# beefocus.net
KiCad netlist of a schematic drawn in EAGLE
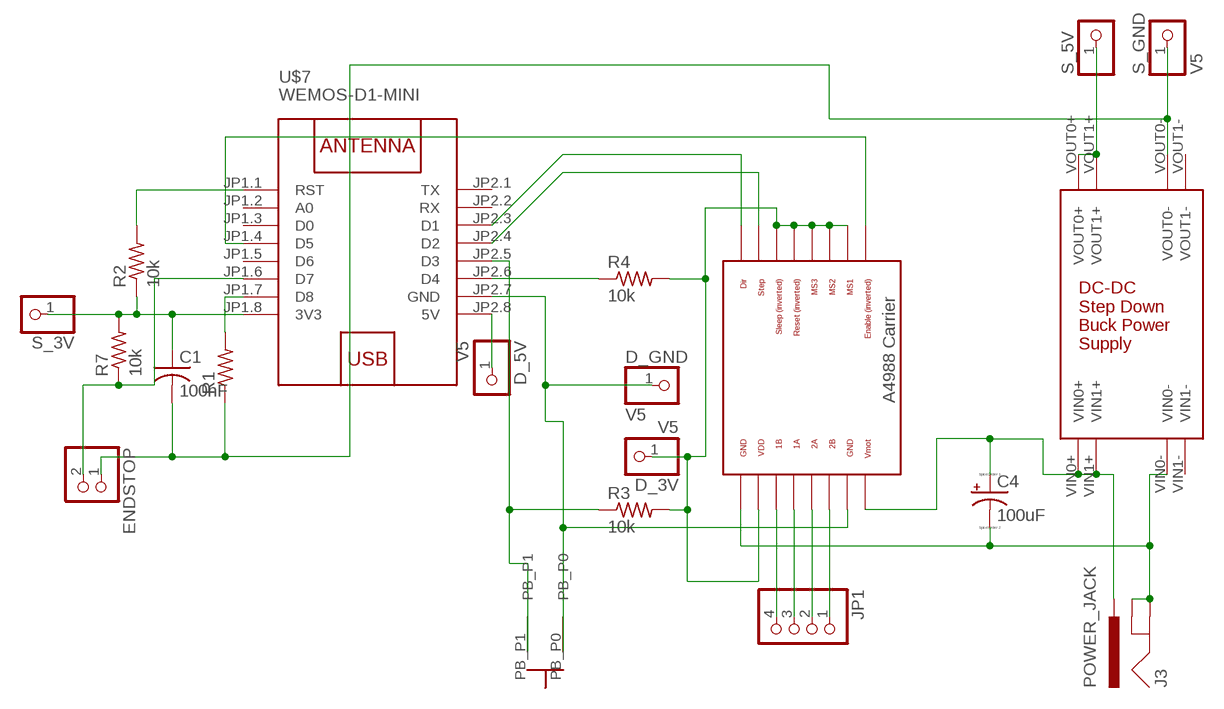
[diagram p0: schematic, sheet 1]

(export (version "E")
  (design (tool "Eeschema 10.0.6"))
  (components
    (comp (ref "C1")
      (value "100nF")
      (footprint "eagle-import:C050-024X044")
      (libsource (lib "eagle-import") (part "C-US050-024X044"))
    )
    (comp (ref "C4")
      (value "100uF")
      (footprint "eagle-import:E3,5-8")
      (libsource (lib "eagle-import") (part "CPOL-USE3.5-8"))
    )
    (comp (ref "D_3V")
      (value "V5")
      (footprint "eagle-import:1X01")
      (libsource (lib "eagle-import") (part "PINHD-1X1"))
    )
    (comp (ref "D_5V")
      (value "V5")
      (footprint "eagle-import:1X01")
      (libsource (lib "eagle-import") (part "PINHD-1X1"))
    )
    (comp (ref "D_GND")
      (value "V5")
      (footprint "eagle-import:1X01")
      (libsource (lib "eagle-import") (part "PINHD-1X1"))
    )
    (comp (ref "ENDSTOP")
      (value "PINHD-1X2/90")
      (footprint "eagle-import:1X02_90")
      (libsource (lib "eagle-import") (part "PINHD-1X2/90"))
    )
    (comp (ref "J3")
      (value "POWER_JACK")
      (footprint "eagle-import:POWER_JACK_PTH")
      (libsource (lib "eagle-import") (part "POWER_JACK"))
    )
    (comp (ref "JP1")
      (value "PINHD-1X4/90")
      (footprint "eagle-import:1X04_90")
      (libsource (lib "eagle-import") (part "PINHD-1X4/90"))
    )
    (comp (ref "R1")
      (value "R-US_0204/7")
      (footprint "eagle-import:0204_7")
      (libsource (lib "eagle-import") (part "R-US_0204/7"))
    )
    (comp (ref "R2")
      (value "10k")
      (footprint "eagle-import:0204_7")
      (libsource (lib "eagle-import") (part "R-US_0204/7"))
    )
    (comp (ref "R3")
      (value "10k")
      (footprint "eagle-import:0309V")
      (libsource (lib "eagle-import") (part "R-US_0309/V"))
    )
    (comp (ref "R4")
      (value "10k")
      (footprint "eagle-import:0204_7")
      (libsource (lib "eagle-import") (part "R-US_0204/7"))
    )
    (comp (ref "R7")
      (value "10k")
      (footprint "eagle-import:0309V")
      (libsource (lib "eagle-import") (part "R-US_0309/V"))
    )
    (comp (ref "S_3V")
      (value "PINHD-1X1")
      (footprint "eagle-import:1X01")
      (libsource (lib "eagle-import") (part "PINHD-1X1"))
    )
    (comp (ref "S_5V")
      (value "PINHD-1X1")
      (footprint "eagle-import:1X01")
      (libsource (lib "eagle-import") (part "PINHD-1X1"))
    )
    (comp (ref "S_GND")
      (value "V5")
      (footprint "eagle-import:1X01")
      (libsource (lib "eagle-import") (part "PINHD-1X1"))
    )
    (comp (ref "U$1")
      (value "POLOLU_A4983CARRIER")
      (footprint "eagle-import:A4988BREAKOUT")
      (libsource (lib "eagle-import") (part "POLOLU_A4983CARRIER"))
    )
    (comp (ref "U$6")
      (value "DCPOWERCONV")
      (footprint "eagle-import:DCPOWERCONV")
      (libsource (lib "eagle-import") (part "DCPOWERCONV"))
    )
    (comp (ref "U$7")
      (value "WEMOS-D1-MINI")
      (footprint "eagle-import:WEMOS-D1-MINI")
      (libsource (lib "eagle-import") (part "WEMOS-D1-MINI"))
    )
    (comp (ref "U$8")
      (value "BUTTON6X6X10MMSIDE")
      (footprint "eagle-import:BUTTON6X6X10MMSIDE")
      (libsource (lib "eagle-import") (part "BUTTON6X6X10MMSIDE"))
    )
  )
  (nets
    (net (code "1") (name "Net-(C1-Pad2)") (class "Default")
      (node (ref "C1") (pin "2") (pinfunction "2_2") (pintype "passive"))
      (node (ref "ENDSTOP") (pin "1") (pinfunction "1_1") (pintype "passive"))
      (node (ref "R1") (pin "1") (pinfunction "1_1") (pintype "passive"))
      (node (ref "S_GND") (pin "1") (pinfunction "1_1") (pintype "passive"))
      (node (ref "U$6") (pin "VOUT0-") (pinfunction "VOUT0-_VOUT0-") (pintype "bidirectional"))
    )
    (net (code "2") (name "Net-(C4-Pad+)") (class "Default")
      (node (ref "C4") (pin "+") (pinfunction "+_+") (pintype "passive"))
      (node (ref "J3") (pin "PWR") (pinfunction "PWR_PWR") (pintype "bidirectional"))
      (node (ref "U$1") (pin "VMOT") (pinfunction "VMOT_VMOT") (pintype "power_in"))
      (node (ref "U$6") (pin "VIN0+") (pinfunction "VIN0+_VIN0+") (pintype "bidirectional"))
      (node (ref "U$6") (pin "VIN1+") (pinfunction "VIN1+_VIN1+") (pintype "bidirectional"))
    )
    (net (code "3") (name "Net-(C4-Pad-)") (class "Default")
      (node (ref "C4") (pin "-") (pinfunction "-_-") (pintype "passive"))
      (node (ref "J3") (pin "GND") (pinfunction "GND_GND") (pintype "bidirectional"))
      (node (ref "J3") (pin "GNDBREAK") (pinfunction "GNDBREAK_GNDBREAK") (pintype "bidirectional"))
      (node (ref "U$1") (pin "GND@0") (pinfunction "GND_GND@0") (pintype "power_in"))
      (node (ref "U$6") (pin "VIN0-") (pinfunction "VIN0-_VIN0-") (pintype "bidirectional"))
    )
    (net (code "4") (name "Net-(JP1-Pad1)") (class "Default")
      (node (ref "JP1") (pin "1") (pinfunction "1_1") (pintype "passive"))
      (node (ref "U$1") (pin "2B") (pinfunction "2B_2B") (pintype "output"))
    )
    (net (code "5") (name "Net-(JP1-Pad2)") (class "Default")
      (node (ref "JP1") (pin "2") (pinfunction "2_2") (pintype "passive"))
      (node (ref "U$1") (pin "2A") (pinfunction "2A_2A") (pintype "output"))
    )
    (net (code "6") (name "Net-(JP1-Pad3)") (class "Default")
      (node (ref "JP1") (pin "3") (pinfunction "3_3") (pintype "passive"))
      (node (ref "U$1") (pin "1A") (pinfunction "1A_1A") (pintype "output"))
    )
    (net (code "7") (name "Net-(JP1-Pad4)") (class "Default")
      (node (ref "JP1") (pin "4") (pinfunction "4_4") (pintype "passive"))
      (node (ref "U$1") (pin "1B") (pinfunction "1B_1B") (pintype "output"))
    )
    (net (code "8") (name "Net-(S_5V-Pad1)") (class "Default")
      (node (ref "S_5V") (pin "1") (pinfunction "1_1") (pintype "passive"))
      (node (ref "U$6") (pin "VOUT0+") (pinfunction "VOUT0+_VOUT0+") (pintype "bidirectional"))
      (node (ref "U$6") (pin "VOUT1+") (pinfunction "VOUT1+_VOUT1+") (pintype "bidirectional"))
    )
    (net (code "9") (name "Net-(U$1-SLEEP)") (class "Default")
      (node (ref "D_3V") (pin "1") (pinfunction "1_1") (pintype "passive"))
      (node (ref "R3") (pin "2") (pinfunction "2_2") (pintype "passive"))
      (node (ref "R4") (pin "2") (pinfunction "2_2") (pintype "passive"))
      (node (ref "U$1") (pin "MS1") (pinfunction "MS1_MS1") (pintype "input"))
      (node (ref "U$1") (pin "MS2") (pinfunction "MS2_MS2") (pintype "input"))
      (node (ref "U$1") (pin "MS3") (pinfunction "MS3_MS3") (pintype "input"))
      (node (ref "U$1") (pin "RST") (pinfunction "RST_RST") (pintype "input"))
      (node (ref "U$1") (pin "SLP") (pinfunction "SLEEP_SLP") (pintype "input"))
      (node (ref "U$1") (pin "VDD") (pinfunction "VDD_VDD") (pintype "power_in"))
    )
    (net (code "10") (name "Net-(U$7-3V3)") (class "Default")
      (node (ref "C1") (pin "1") (pinfunction "1_1") (pintype "passive"))
      (node (ref "R2") (pin "1") (pinfunction "1_1") (pintype "passive"))
      (node (ref "R7") (pin "2") (pinfunction "2_2") (pintype "passive"))
      (node (ref "S_3V") (pin "1") (pinfunction "1_1") (pintype "passive"))
      (node (ref "U$7") (pin "JP1.8") (pinfunction "3V3_JP1.8") (pintype "power_in"))
    )
    (net (code "11") (name "Net-(U$7-5V)") (class "Default")
      (node (ref "D_5V") (pin "1") (pinfunction "1_1") (pintype "passive"))
      (node (ref "U$7") (pin "JP2.8") (pinfunction "5V_JP2.8") (pintype "power_in"))
    )
    (net (code "12") (name "Net-(U$7-D1)") (class "Default")
      (node (ref "U$1") (pin "DIR") (pinfunction "DIR_DIR") (pintype "input"))
      (node (ref "U$7") (pin "JP2.3") (pinfunction "D1_JP2.3") (pintype "bidirectional"))
    )
    (net (code "13") (name "Net-(U$7-D2)") (class "Default")
      (node (ref "U$1") (pin "STEP") (pinfunction "STEP_STEP") (pintype "input"))
      (node (ref "U$7") (pin "JP2.4") (pinfunction "D2_JP2.4") (pintype "bidirectional"))
    )
    (net (code "14") (name "Net-(U$7-D3)") (class "Default")
      (node (ref "R3") (pin "1") (pinfunction "1_1") (pintype "passive"))
      (node (ref "U$7") (pin "JP2.5") (pinfunction "D3_JP2.5") (pintype "bidirectional"))
      (node (ref "U$8") (pin "PB_P1") (pinfunction "PB_P1_PB_P1") (pintype "bidirectional"))
    )
    (net (code "15") (name "Net-(U$7-D4)") (class "Default")
      (node (ref "R4") (pin "1") (pinfunction "1_1") (pintype "passive"))
      (node (ref "U$7") (pin "JP2.6") (pinfunction "D4_JP2.6") (pintype "bidirectional"))
    )
    (net (code "16") (name "Net-(U$7-D5)") (class "Default")
      (node (ref "U$1") (pin "EN") (pinfunction "EN_EN") (pintype "input"))
      (node (ref "U$7") (pin "JP1.4") (pinfunction "D5_JP1.4") (pintype "bidirectional"))
    )
    (net (code "17") (name "Net-(U$7-D7)") (class "Default")
      (node (ref "ENDSTOP") (pin "2") (pinfunction "2_2") (pintype "passive"))
      (node (ref "R7") (pin "1") (pinfunction "1_1") (pintype "passive"))
      (node (ref "U$7") (pin "JP1.6") (pinfunction "D7_JP1.6") (pintype "bidirectional"))
    )
    (net (code "18") (name "Net-(U$7-D8)") (class "Default")
      (node (ref "R1") (pin "2") (pinfunction "2_2") (pintype "passive"))
      (node (ref "U$7") (pin "JP1.7") (pinfunction "D8_JP1.7") (pintype "bidirectional"))
    )
    (net (code "19") (name "Net-(U$7-GND)") (class "Default")
      (node (ref "D_GND") (pin "1") (pinfunction "1_1") (pintype "passive"))
      (node (ref "U$1") (pin "GND") (pinfunction "GND_GND") (pintype "power_in"))
      (node (ref "U$7") (pin "JP2.7") (pinfunction "GND_JP2.7") (pintype "power_in"))
      (node (ref "U$8") (pin "PB_P0") (pinfunction "PB_P0_PB_P0") (pintype "bidirectional"))
    )
    (net (code "20") (name "Net-(U$7-RST)") (class "Default")
      (node (ref "R2") (pin "2") (pinfunction "2_2") (pintype "passive"))
      (node (ref "U$7") (pin "JP1.1") (pinfunction "RST_JP1.1") (pintype "bidirectional"))
    )
    (net (code "21") (name "unconnected-(U$6-PadVIN1-)") (class "Default")
      (node (ref "U$6") (pin "VIN1-") (pinfunction "VIN1-_VIN1-") (pintype "bidirectional"))
    )
    (net (code "22") (name "unconnected-(U$6-PadVOUT1-)") (class "Default")
      (node (ref "U$6") (pin "VOUT1-") (pinfunction "VOUT1-_VOUT1-") (pintype "bidirectional"))
    )
    (net (code "23") (name "unconnected-(U$7-A0-PadJP1.2)") (class "Default")
      (node (ref "U$7") (pin "JP1.2") (pinfunction "A0_JP1.2") (pintype "bidirectional"))
    )
    (net (code "24") (name "unconnected-(U$7-D0-PadJP1.3)") (class "Default")
      (node (ref "U$7") (pin "JP1.3") (pinfunction "D0_JP1.3") (pintype "bidirectional"))
    )
    (net (code "25") (name "unconnected-(U$7-D6-PadJP1.5)") (class "Default")
      (node (ref "U$7") (pin "JP1.5") (pinfunction "D6_JP1.5") (pintype "bidirectional"))
    )
    (net (code "26") (name "unconnected-(U$7-RX-PadJP2.2)") (class "Default")
      (node (ref "U$7") (pin "JP2.2") (pinfunction "RX_JP2.2") (pintype "bidirectional"))
    )
    (net (code "27") (name "unconnected-(U$7-TX-PadJP2.1)") (class "Default")
      (node (ref "U$7") (pin "JP2.1") (pinfunction "TX_JP2.1") (pintype "bidirectional"))
    )
  )
)
